# 38kHzSensorRevA2.net
KiCad netlist of a schematic drawn in EAGLE
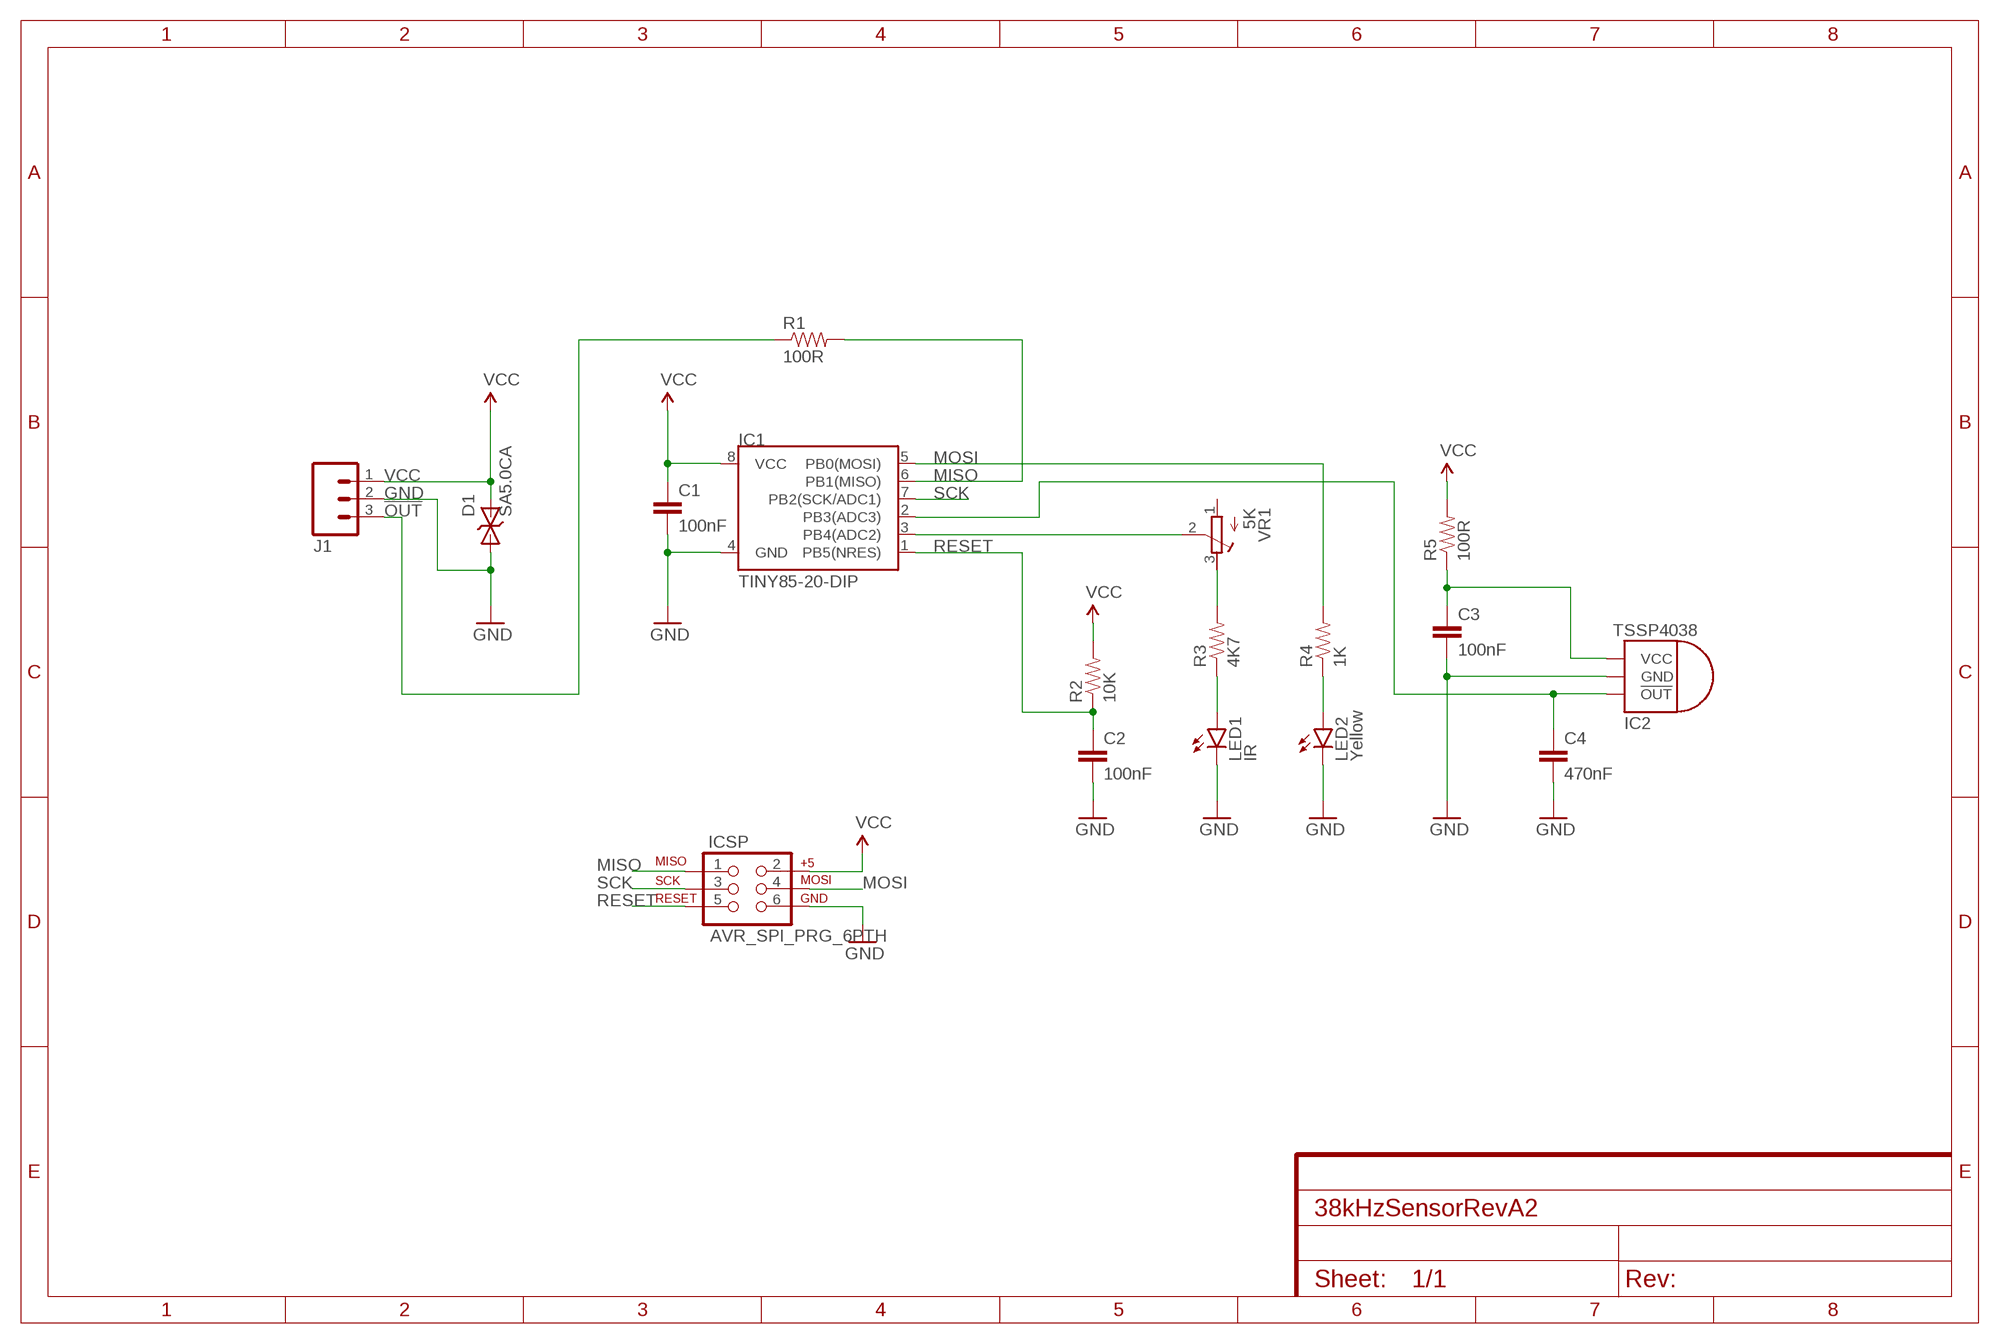
[diagram p0: schematic, sheet 1]

(export (version "E")
  (design (tool "Eeschema 10.0.6"))
  (components
    (comp (ref "C1")
      (value "100nF")
      (footprint "eagle-import:CAP-PTH-SMALL")
      (libsource (lib "eagle-import") (part "CAPPTH"))
    )
    (comp (ref "C2")
      (value "100nF")
      (footprint "eagle-import:CAP-PTH-SMALL")
      (libsource (lib "eagle-import") (part "CAPPTH"))
    )
    (comp (ref "C3")
      (value "100nF")
      (footprint "eagle-import:CAP-PTH-SMALL")
      (libsource (lib "eagle-import") (part "CAPPTH"))
    )
    (comp (ref "C4")
      (value "470nF")
      (footprint "eagle-import:CAP-PTH-5MM")
      (libsource (lib "eagle-import") (part "CAPPTH1"))
    )
    (comp (ref "D1")
      (value "SA5.0CA")
      (footprint "eagle-import:DO41_TVS")
      (libsource (lib "eagle-import") (part "SA5.0CA"))
    )
    (comp (ref "IC1")
      (value "TINY85-20-DIP")
      (footprint "eagle-import:DIP08")
      (libsource (lib "eagle-import") (part "ATTINY45TINY85-20-DIP"))
    )
    (comp (ref "IC2")
      (value "TSSP4038EDGE")
      (footprint "eagle-import:TSSP4038_PKG_EDGE")
      (libsource (lib "eagle-import") (part "TSSP4038EDGE"))
    )
    (comp (ref "ICSP")
      (value "AVR_SPI_PRG_6PTH")
      (footprint "eagle-import:2X3")
      (libsource (lib "eagle-import") (part "AVR_SPI_PRG_6PTH"))
    )
    (comp (ref "J1")
      (value "M03PTH")
      (footprint "eagle-import:1X03")
      (libsource (lib "eagle-import") (part "M03PTH"))
    )
    (comp (ref "LED1")
      (value "IR")
      (footprint "eagle-import:LED5MM")
      (libsource (lib "eagle-import") (part "LED5MM"))
    )
    (comp (ref "LED2")
      (value "Yellow")
      (footprint "eagle-import:LED3MM")
      (libsource (lib "eagle-import") (part "LED3MM"))
    )
    (comp (ref "R1")
      (value "100R")
      (footprint "eagle-import:AXIAL-0.4")
      (libsource (lib "eagle-import") (part "RESISTORPTH-1/4W"))
    )
    (comp (ref "R2")
      (value "10K")
      (footprint "eagle-import:AXIAL-0.4")
      (libsource (lib "eagle-import") (part "RESISTORPTH-1/4W"))
    )
    (comp (ref "R3")
      (value "4K7")
      (footprint "eagle-import:AXIAL-0.4")
      (libsource (lib "eagle-import") (part "RESISTORPTH-1/4W"))
    )
    (comp (ref "R4")
      (value "1K")
      (footprint "eagle-import:AXIAL-0.4")
      (libsource (lib "eagle-import") (part "RESISTORPTH-1/4W"))
    )
    (comp (ref "R5")
      (value "100R")
      (footprint "eagle-import:AXIAL-0.4")
      (libsource (lib "eagle-import") (part "RESISTORPTH-1/4W"))
    )
    (comp (ref "VR1")
      (value "5K")
      (footprint "eagle-import:RTRIM3296X")
      (libsource (lib "eagle-import") (part "R-TRIMM3296X"))
    )
  )
  (nets
    (net (code "1") (name "/MISO") (class "Default")
      (node (ref "IC1") (pin "6") (pinfunction "PB1(MISO)_6") (pintype "bidirectional"))
      (node (ref "ICSP") (pin "1") (pinfunction "1_1") (pintype "passive"))
      (node (ref "R1") (pin "P$2") (pinfunction "2_P$2") (pintype "passive"))
    )
    (net (code "2") (name "/MOSI") (class "Default")
      (node (ref "IC1") (pin "5") (pinfunction "PB0(MOSI)_5") (pintype "bidirectional"))
      (node (ref "ICSP") (pin "4") (pinfunction "4_4") (pintype "passive"))
      (node (ref "R4") (pin "P$2") (pinfunction "2_P$2") (pintype "passive"))
    )
    (net (code "3") (name "/RESET") (class "Default")
      (node (ref "C2") (pin "1") (pinfunction "1_1") (pintype "passive"))
      (node (ref "IC1") (pin "1") (pinfunction "PB5(NRES)_1") (pintype "bidirectional"))
      (node (ref "ICSP") (pin "5") (pinfunction "5_5") (pintype "passive"))
      (node (ref "R2") (pin "P$1") (pinfunction "1_P$1") (pintype "passive"))
    )
    (net (code "4") (name "/SCK") (class "Default")
      (node (ref "IC1") (pin "7") (pinfunction "PB2(SCK/ADC1)_7") (pintype "bidirectional"))
      (node (ref "ICSP") (pin "3") (pinfunction "3_3") (pintype "passive"))
    )
    (net (code "5") (name "/~{OUT}") (class "Default")
      (node (ref "J1") (pin "3") (pinfunction "3_3") (pintype "passive"))
      (node (ref "R1") (pin "P$1") (pinfunction "1_P$1") (pintype "passive"))
    )
    (net (code "6") (name "GND") (class "Default")
      (node (ref "C1") (pin "2") (pinfunction "2_2") (pintype "passive"))
      (node (ref "C2") (pin "2") (pinfunction "2_2") (pintype "passive"))
      (node (ref "C3") (pin "2") (pinfunction "2_2") (pintype "passive"))
      (node (ref "C4") (pin "2") (pinfunction "2_2") (pintype "passive"))
      (node (ref "D1") (pin "A") (pinfunction "A_A") (pintype "passive"))
      (node (ref "IC1") (pin "4") (pinfunction "GND_4") (pintype "bidirectional"))
      (node (ref "IC2") (pin "GND") (pinfunction "GND_GND") (pintype "bidirectional"))
      (node (ref "ICSP") (pin "6") (pinfunction "6_6") (pintype "passive"))
      (node (ref "J1") (pin "2") (pinfunction "2_2") (pintype "passive"))
      (node (ref "LED1") (pin "K") (pinfunction "C_K") (pintype "passive"))
      (node (ref "LED2") (pin "K") (pinfunction "C_K") (pintype "passive"))
    )
    (net (code "7") (name "Net-(IC1-PB3(ADC3))") (class "Default")
      (node (ref "C4") (pin "1") (pinfunction "1_1") (pintype "passive"))
      (node (ref "IC1") (pin "2") (pinfunction "PB3(ADC3)_2") (pintype "bidirectional"))
      (node (ref "IC2") (pin "OUT") (pinfunction "~{OUT}_OUT") (pintype "bidirectional"))
    )
    (net (code "8") (name "Net-(IC1-PB4(ADC2))") (class "Default")
      (node (ref "IC1") (pin "3") (pinfunction "PB4(ADC2)_3") (pintype "bidirectional"))
      (node (ref "VR1") (pin "2") (pinfunction "S_2") (pintype "passive"))
    )
    (net (code "9") (name "Net-(R3-1)") (class "Default")
      (node (ref "LED1") (pin "A") (pinfunction "A_A") (pintype "passive"))
      (node (ref "R3") (pin "P$1") (pinfunction "1_P$1") (pintype "passive"))
    )
    (net (code "10") (name "Net-(R3-2)") (class "Default")
      (node (ref "R3") (pin "P$2") (pinfunction "2_P$2") (pintype "passive"))
      (node (ref "VR1") (pin "3") (pinfunction "E_3") (pintype "passive"))
    )
    (net (code "11") (name "Net-(R4-1)") (class "Default")
      (node (ref "LED2") (pin "A") (pinfunction "A_A") (pintype "passive"))
      (node (ref "R4") (pin "P$1") (pinfunction "1_P$1") (pintype "passive"))
    )
    (net (code "12") (name "Net-(R5-1)") (class "Default")
      (node (ref "C3") (pin "1") (pinfunction "1_1") (pintype "passive"))
      (node (ref "IC2") (pin "VCC") (pinfunction "VCC_VCC") (pintype "bidirectional"))
      (node (ref "R5") (pin "P$1") (pinfunction "1_P$1") (pintype "passive"))
    )
    (net (code "13") (name "VCC") (class "Default")
      (node (ref "C1") (pin "1") (pinfunction "1_1") (pintype "passive"))
      (node (ref "D1") (pin "C") (pinfunction "C_C") (pintype "passive"))
      (node (ref "IC1") (pin "8") (pinfunction "VCC_8") (pintype "bidirectional"))
      (node (ref "ICSP") (pin "2") (pinfunction "2_2") (pintype "passive"))
      (node (ref "J1") (pin "1") (pinfunction "1_1") (pintype "passive"))
      (node (ref "R2") (pin "P$2") (pinfunction "2_P$2") (pintype "passive"))
      (node (ref "R5") (pin "P$2") (pinfunction "2_P$2") (pintype "passive"))
    )
    (net (code "14") (name "unconnected-(VR1-A-Pad1)") (class "Default")
      (node (ref "VR1") (pin "1") (pinfunction "A_1") (pintype "passive"))
    )
  )
)
